# BreakoutV3.net
KiCad netlist of a schematic drawn in EAGLE
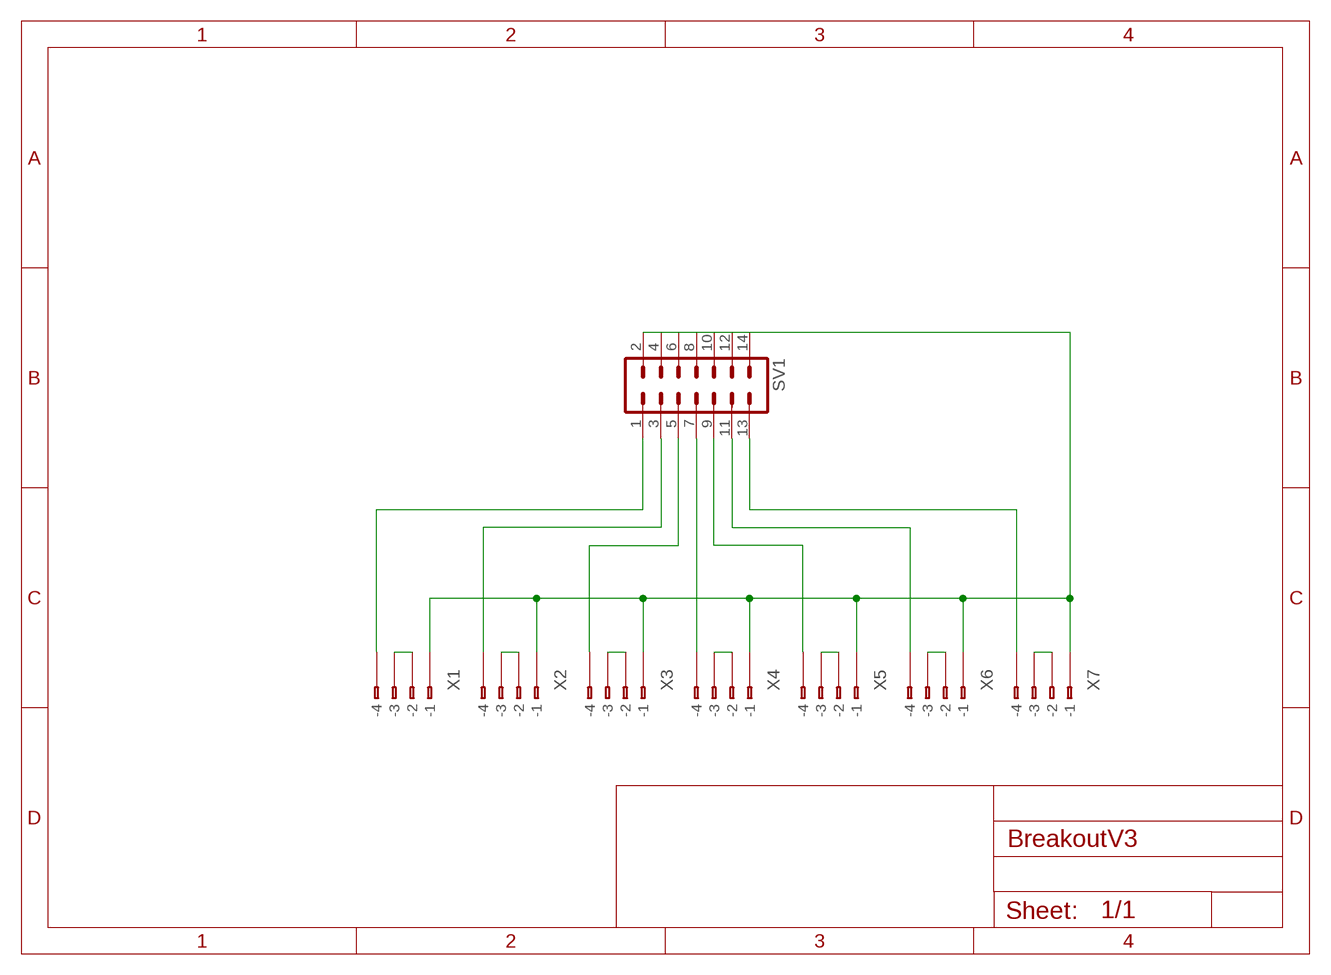
[diagram p0: schematic, sheet 1]

(export (version "E")
  (design (tool "Eeschema 10.0.6"))
  (components
    (comp (ref "SV1")
      (value "ML14")
      (footprint "eagle-import:ML14")
      (libsource (lib "eagle-import") (part "ML14"))
    )
    (comp (ref "X1")
      (value "233-104")
      (footprint "eagle-import:233-104")
      (libsource (lib "eagle-import") (part "233-104"))
    )
    (comp (ref "X2")
      (value "233-104")
      (footprint "eagle-import:233-104")
      (libsource (lib "eagle-import") (part "233-104"))
    )
    (comp (ref "X3")
      (value "233-104")
      (footprint "eagle-import:233-104")
      (libsource (lib "eagle-import") (part "233-104"))
    )
    (comp (ref "X4")
      (value "233-104")
      (footprint "eagle-import:233-104")
      (libsource (lib "eagle-import") (part "233-104"))
    )
    (comp (ref "X5")
      (value "233-104")
      (footprint "eagle-import:233-104")
      (libsource (lib "eagle-import") (part "233-104"))
    )
    (comp (ref "X6")
      (value "233-104")
      (footprint "eagle-import:233-104")
      (libsource (lib "eagle-import") (part "233-104"))
    )
    (comp (ref "X7")
      (value "233-104")
      (footprint "eagle-import:233-104")
      (libsource (lib "eagle-import") (part "233-104"))
    )
  )
  (nets
    (net (code "1") (name "Net-(X1-B-1)") (class "Default")
      (node (ref "SV1") (pin "10") (pinfunction "10_10") (pintype "passive"))
      (node (ref "SV1") (pin "12") (pinfunction "12_12") (pintype "passive"))
      (node (ref "SV1") (pin "14") (pinfunction "14_14") (pintype "passive"))
      (node (ref "SV1") (pin "2") (pinfunction "2_2") (pintype "passive"))
      (node (ref "SV1") (pin "4") (pinfunction "4_4") (pintype "passive"))
      (node (ref "SV1") (pin "6") (pinfunction "6_6") (pintype "passive"))
      (node (ref "SV1") (pin "8") (pinfunction "8_8") (pintype "passive"))
      (node (ref "X1") (pin "B1") (pinfunction "B-1_B1") (pintype "passive"))
      (node (ref "X2") (pin "B1") (pinfunction "B-1_B1") (pintype "passive"))
      (node (ref "X3") (pin "B1") (pinfunction "B-1_B1") (pintype "passive"))
      (node (ref "X4") (pin "B1") (pinfunction "B-1_B1") (pintype "passive"))
      (node (ref "X5") (pin "B1") (pinfunction "B-1_B1") (pintype "passive"))
      (node (ref "X6") (pin "B1") (pinfunction "B-1_B1") (pintype "passive"))
      (node (ref "X7") (pin "B1") (pinfunction "B-1_B1") (pintype "passive"))
    )
    (net (code "2") (name "Net-(X1-B-2)") (class "Default")
      (node (ref "X1") (pin "B2") (pinfunction "B-2_B2") (pintype "passive"))
      (node (ref "X1") (pin "B3") (pinfunction "B-3_B3") (pintype "passive"))
    )
    (net (code "3") (name "Net-(X1-B-4)") (class "Default")
      (node (ref "SV1") (pin "1") (pinfunction "1_1") (pintype "passive"))
      (node (ref "X1") (pin "B4") (pinfunction "B-4_B4") (pintype "passive"))
    )
    (net (code "4") (name "Net-(X2-B-2)") (class "Default")
      (node (ref "X2") (pin "B2") (pinfunction "B-2_B2") (pintype "passive"))
      (node (ref "X2") (pin "B3") (pinfunction "B-3_B3") (pintype "passive"))
    )
    (net (code "5") (name "Net-(X2-B-4)") (class "Default")
      (node (ref "SV1") (pin "3") (pinfunction "3_3") (pintype "passive"))
      (node (ref "X2") (pin "B4") (pinfunction "B-4_B4") (pintype "passive"))
    )
    (net (code "6") (name "Net-(X3-B-2)") (class "Default")
      (node (ref "X3") (pin "B2") (pinfunction "B-2_B2") (pintype "passive"))
      (node (ref "X3") (pin "B3") (pinfunction "B-3_B3") (pintype "passive"))
    )
    (net (code "7") (name "Net-(X3-B-4)") (class "Default")
      (node (ref "SV1") (pin "5") (pinfunction "5_5") (pintype "passive"))
      (node (ref "X3") (pin "B4") (pinfunction "B-4_B4") (pintype "passive"))
    )
    (net (code "8") (name "Net-(X4-B-2)") (class "Default")
      (node (ref "X4") (pin "B2") (pinfunction "B-2_B2") (pintype "passive"))
      (node (ref "X4") (pin "B3") (pinfunction "B-3_B3") (pintype "passive"))
    )
    (net (code "9") (name "Net-(X4-B-4)") (class "Default")
      (node (ref "SV1") (pin "7") (pinfunction "7_7") (pintype "passive"))
      (node (ref "X4") (pin "B4") (pinfunction "B-4_B4") (pintype "passive"))
    )
    (net (code "10") (name "Net-(X5-B-2)") (class "Default")
      (node (ref "X5") (pin "B2") (pinfunction "B-2_B2") (pintype "passive"))
      (node (ref "X5") (pin "B3") (pinfunction "B-3_B3") (pintype "passive"))
    )
    (net (code "11") (name "Net-(X5-B-4)") (class "Default")
      (node (ref "SV1") (pin "9") (pinfunction "9_9") (pintype "passive"))
      (node (ref "X5") (pin "B4") (pinfunction "B-4_B4") (pintype "passive"))
    )
    (net (code "12") (name "Net-(X6-B-2)") (class "Default")
      (node (ref "X6") (pin "B2") (pinfunction "B-2_B2") (pintype "passive"))
      (node (ref "X6") (pin "B3") (pinfunction "B-3_B3") (pintype "passive"))
    )
    (net (code "13") (name "Net-(X6-B-4)") (class "Default")
      (node (ref "SV1") (pin "11") (pinfunction "11_11") (pintype "passive"))
      (node (ref "X6") (pin "B4") (pinfunction "B-4_B4") (pintype "passive"))
    )
    (net (code "14") (name "Net-(X7-B-2)") (class "Default")
      (node (ref "X7") (pin "B2") (pinfunction "B-2_B2") (pintype "passive"))
      (node (ref "X7") (pin "B3") (pinfunction "B-3_B3") (pintype "passive"))
    )
    (net (code "15") (name "Net-(X7-B-4)") (class "Default")
      (node (ref "SV1") (pin "13") (pinfunction "13_13") (pintype "passive"))
      (node (ref "X7") (pin "B4") (pinfunction "B-4_B4") (pintype "passive"))
    )
    (net (code "16") (name "unconnected-(X1--1-PadA1)") (class "Default")
      (node (ref "X1") (pin "A1") (pinfunction "-1_A1") (pintype "passive"))
    )
    (net (code "17") (name "unconnected-(X1--2-PadA2)") (class "Default")
      (node (ref "X1") (pin "A2") (pinfunction "-2_A2") (pintype "passive"))
    )
    (net (code "18") (name "unconnected-(X1--3-PadA3)") (class "Default")
      (node (ref "X1") (pin "A3") (pinfunction "-3_A3") (pintype "passive"))
    )
    (net (code "19") (name "unconnected-(X1--4-PadA4)") (class "Default")
      (node (ref "X1") (pin "A4") (pinfunction "-4_A4") (pintype "passive"))
    )
    (net (code "20") (name "unconnected-(X2--1-PadA1)") (class "Default")
      (node (ref "X2") (pin "A1") (pinfunction "-1_A1") (pintype "passive"))
    )
    (net (code "21") (name "unconnected-(X2--2-PadA2)") (class "Default")
      (node (ref "X2") (pin "A2") (pinfunction "-2_A2") (pintype "passive"))
    )
    (net (code "22") (name "unconnected-(X2--3-PadA3)") (class "Default")
      (node (ref "X2") (pin "A3") (pinfunction "-3_A3") (pintype "passive"))
    )
    (net (code "23") (name "unconnected-(X2--4-PadA4)") (class "Default")
      (node (ref "X2") (pin "A4") (pinfunction "-4_A4") (pintype "passive"))
    )
    (net (code "24") (name "unconnected-(X3--1-PadA1)") (class "Default")
      (node (ref "X3") (pin "A1") (pinfunction "-1_A1") (pintype "passive"))
    )
    (net (code "25") (name "unconnected-(X3--2-PadA2)") (class "Default")
      (node (ref "X3") (pin "A2") (pinfunction "-2_A2") (pintype "passive"))
    )
    (net (code "26") (name "unconnected-(X3--3-PadA3)") (class "Default")
      (node (ref "X3") (pin "A3") (pinfunction "-3_A3") (pintype "passive"))
    )
    (net (code "27") (name "unconnected-(X3--4-PadA4)") (class "Default")
      (node (ref "X3") (pin "A4") (pinfunction "-4_A4") (pintype "passive"))
    )
    (net (code "28") (name "unconnected-(X4--1-PadA1)") (class "Default")
      (node (ref "X4") (pin "A1") (pinfunction "-1_A1") (pintype "passive"))
    )
    (net (code "29") (name "unconnected-(X4--2-PadA2)") (class "Default")
      (node (ref "X4") (pin "A2") (pinfunction "-2_A2") (pintype "passive"))
    )
    (net (code "30") (name "unconnected-(X4--3-PadA3)") (class "Default")
      (node (ref "X4") (pin "A3") (pinfunction "-3_A3") (pintype "passive"))
    )
    (net (code "31") (name "unconnected-(X4--4-PadA4)") (class "Default")
      (node (ref "X4") (pin "A4") (pinfunction "-4_A4") (pintype "passive"))
    )
    (net (code "32") (name "unconnected-(X5--1-PadA1)") (class "Default")
      (node (ref "X5") (pin "A1") (pinfunction "-1_A1") (pintype "passive"))
    )
    (net (code "33") (name "unconnected-(X5--2-PadA2)") (class "Default")
      (node (ref "X5") (pin "A2") (pinfunction "-2_A2") (pintype "passive"))
    )
    (net (code "34") (name "unconnected-(X5--3-PadA3)") (class "Default")
      (node (ref "X5") (pin "A3") (pinfunction "-3_A3") (pintype "passive"))
    )
    (net (code "35") (name "unconnected-(X5--4-PadA4)") (class "Default")
      (node (ref "X5") (pin "A4") (pinfunction "-4_A4") (pintype "passive"))
    )
    (net (code "36") (name "unconnected-(X6--1-PadA1)") (class "Default")
      (node (ref "X6") (pin "A1") (pinfunction "-1_A1") (pintype "passive"))
    )
    (net (code "37") (name "unconnected-(X6--2-PadA2)") (class "Default")
      (node (ref "X6") (pin "A2") (pinfunction "-2_A2") (pintype "passive"))
    )
    (net (code "38") (name "unconnected-(X6--3-PadA3)") (class "Default")
      (node (ref "X6") (pin "A3") (pinfunction "-3_A3") (pintype "passive"))
    )
    (net (code "39") (name "unconnected-(X6--4-PadA4)") (class "Default")
      (node (ref "X6") (pin "A4") (pinfunction "-4_A4") (pintype "passive"))
    )
    (net (code "40") (name "unconnected-(X7--1-PadA1)") (class "Default")
      (node (ref "X7") (pin "A1") (pinfunction "-1_A1") (pintype "passive"))
    )
    (net (code "41") (name "unconnected-(X7--2-PadA2)") (class "Default")
      (node (ref "X7") (pin "A2") (pinfunction "-2_A2") (pintype "passive"))
    )
    (net (code "42") (name "unconnected-(X7--3-PadA3)") (class "Default")
      (node (ref "X7") (pin "A3") (pinfunction "-3_A3") (pintype "passive"))
    )
    (net (code "43") (name "unconnected-(X7--4-PadA4)") (class "Default")
      (node (ref "X7") (pin "A4") (pinfunction "-4_A4") (pintype "passive"))
    )
  )
)
